# Schaltplan_Test_2.net
KiCad netlist of a schematic drawn in EAGLE
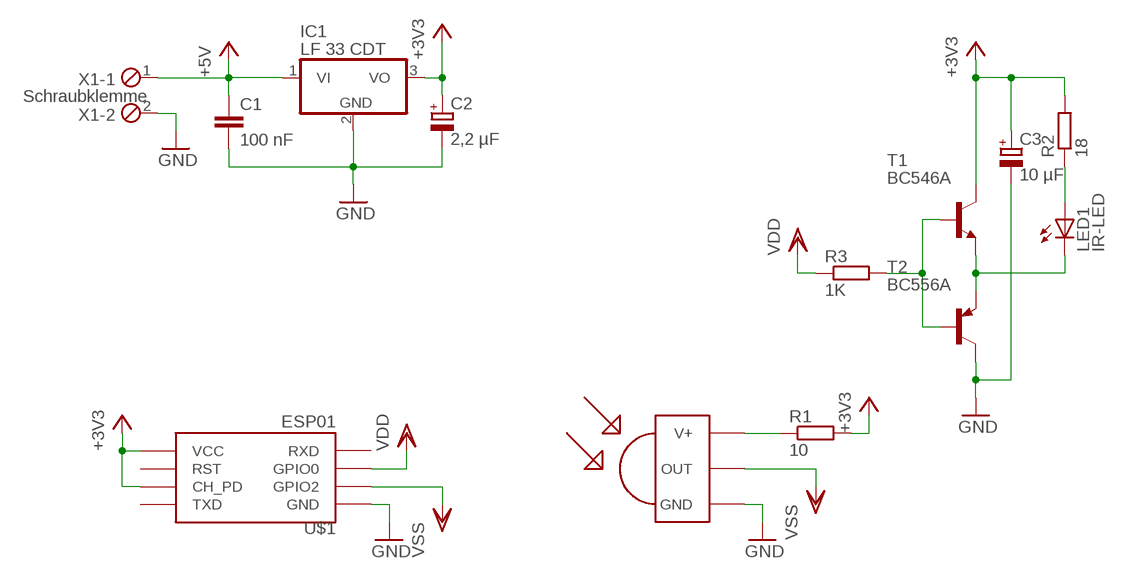
[diagram p0: schematic, sheet 1]

(export (version "E")
  (design (tool "Eeschema 10.0.6"))
  (components
    (comp (ref "C1")
      (value "100 nF")
      (footprint "eagle-import:C025-024X044")
      (libsource (lib "eagle-import") (part "C-EU025-024X044"))
    )
    (comp (ref "C2")
      (value "2,2 µF")
      (footprint "eagle-import:E2,5-5")
      (libsource (lib "eagle-import") (part "CPOL-EUE2.5-5"))
    )
    (comp (ref "C3")
      (value "10 µF")
      (footprint "eagle-import:E2,5-5")
      (libsource (lib "eagle-import") (part "CPOL-EUE2.5-5"))
    )
    (comp (ref "IC1")
      (value "LF 33 CDT")
      (footprint "eagle-import:TO220V")
      (libsource (lib "eagle-import") (part "MC78MT05AB"))
    )
    (comp (ref "IR-TRANSMITTER")
      (value "TSOP1833")
      (footprint "eagle-import:TSOP18XX")
      (libsource (lib "eagle-import") (part "TSOP1833"))
    )
    (comp (ref "LED1")
      (value "IR-LED")
      (footprint "eagle-import:LED5MM")
      (libsource (lib "eagle-import") (part "LED5MM"))
    )
    (comp (ref "R1")
      (value "10")
      (footprint "eagle-import:0204_7")
      (libsource (lib "eagle-import") (part "R-EU_0204/7"))
    )
    (comp (ref "R2")
      (value "18")
      (footprint "eagle-import:0204_5")
      (libsource (lib "eagle-import") (part "R-EU_0204/5"))
    )
    (comp (ref "R3")
      (value "1K")
      (footprint "eagle-import:0204_5")
      (libsource (lib "eagle-import") (part "R-EU_0204/5"))
    )
    (comp (ref "T1")
      (value "BC546A")
      (footprint "eagle-import:TO92-EBC")
      (libsource (lib "eagle-import") (part "BC546A"))
    )
    (comp (ref "T2")
      (value "BC556A")
      (footprint "eagle-import:TO92-EBC")
      (libsource (lib "eagle-import") (part "BC556A"))
    )
    (comp (ref "U$1")
      (value "ESP01")
      (footprint "eagle-import:ESP01")
      (libsource (lib "eagle-import") (part "ESP01"))
    )
    (comp (ref "X1")
      (value "Schraubklemme")
      (footprint "eagle-import:2POL254")
      (libsource (lib "eagle-import") (part "MPT2"))
    )
  )
  (nets
    (net (code "1") (name "+3V3") (class "Default")
      (node (ref "C2") (pin "+") (pinfunction "+_+") (pintype "passive"))
      (node (ref "C3") (pin "+") (pinfunction "+_+") (pintype "passive"))
      (node (ref "IC1") (pin "3") (pinfunction "VO_3") (pintype "passive"))
      (node (ref "R1") (pin "2") (pinfunction "2_2") (pintype "passive"))
      (node (ref "R2") (pin "2") (pinfunction "2_2") (pintype "passive"))
      (node (ref "T1") (pin "C") (pinfunction "C_C") (pintype "passive"))
      (node (ref "U$1") (pin "CH_PD") (pinfunction "CH_PD_CH_PD") (pintype "bidirectional"))
      (node (ref "U$1") (pin "VCC") (pinfunction "VCC_VCC") (pintype "bidirectional"))
    )
    (net (code "2") (name "+5V") (class "Default")
      (node (ref "C1") (pin "1") (pinfunction "1_1") (pintype "passive"))
      (node (ref "IC1") (pin "1") (pinfunction "VI_1") (pintype "input"))
      (node (ref "X1") (pin "1") (pinfunction "1_1") (pintype "passive"))
    )
    (net (code "3") (name "GND") (class "Default")
      (node (ref "C1") (pin "2") (pinfunction "2_2") (pintype "passive"))
      (node (ref "C2") (pin "-") (pinfunction "-_-") (pintype "passive"))
      (node (ref "C3") (pin "-") (pinfunction "-_-") (pintype "passive"))
      (node (ref "IC1") (pin "2") (pinfunction "GND_2") (pintype "passive"))
      (node (ref "IR-TRANSMITTER") (pin "GND") (pinfunction "GND_GND") (pintype "bidirectional"))
      (node (ref "T2") (pin "C") (pinfunction "C_C") (pintype "passive"))
      (node (ref "U$1") (pin "GND") (pinfunction "GND_GND") (pintype "bidirectional"))
      (node (ref "X1") (pin "2") (pinfunction "1_2") (pintype "passive"))
    )
    (net (code "4") (name "Net-(IR-TRANSMITTER-V+)") (class "Default")
      (node (ref "IR-TRANSMITTER") (pin "VCC") (pinfunction "V+_VCC") (pintype "bidirectional"))
      (node (ref "R1") (pin "1") (pinfunction "1_1") (pintype "passive"))
    )
    (net (code "5") (name "Net-(LED1-C)") (class "Default")
      (node (ref "LED1") (pin "K") (pinfunction "C_K") (pintype "passive"))
      (node (ref "T1") (pin "E") (pinfunction "E_E") (pintype "passive"))
      (node (ref "T2") (pin "E") (pinfunction "E_E") (pintype "passive"))
    )
    (net (code "6") (name "Net-(LED1-PadA)") (class "Default")
      (node (ref "LED1") (pin "A") (pinfunction "A_A") (pintype "passive"))
      (node (ref "R2") (pin "1") (pinfunction "1_1") (pintype "passive"))
    )
    (net (code "7") (name "Net-(R3-Pad2)") (class "Default")
      (node (ref "R3") (pin "2") (pinfunction "2_2") (pintype "passive"))
      (node (ref "T1") (pin "B") (pinfunction "B_B") (pintype "passive"))
      (node (ref "T2") (pin "B") (pinfunction "B_B") (pintype "passive"))
    )
    (net (code "8") (name "VDD") (class "Default")
      (node (ref "R3") (pin "1") (pinfunction "1_1") (pintype "passive"))
      (node (ref "U$1") (pin "GPIO0") (pinfunction "GPIO0_GPIO0") (pintype "bidirectional"))
    )
    (net (code "9") (name "VSS") (class "Default")
      (node (ref "IR-TRANSMITTER") (pin "OUT") (pinfunction "OUT_OUT") (pintype "bidirectional"))
      (node (ref "U$1") (pin "GPIO2") (pinfunction "GPIO2_GPIO2") (pintype "bidirectional"))
    )
    (net (code "10") (name "unconnected-(U$1-PadRST)") (class "Default")
      (node (ref "U$1") (pin "RST") (pinfunction "RST_RST") (pintype "bidirectional"))
    )
    (net (code "11") (name "unconnected-(U$1-RXD-PadRX)") (class "Default")
      (node (ref "U$1") (pin "RX") (pinfunction "RXD_RX") (pintype "bidirectional"))
    )
    (net (code "12") (name "unconnected-(U$1-TXD-PadTX)") (class "Default")
      (node (ref "U$1") (pin "TX") (pinfunction "TXD_TX") (pintype "bidirectional"))
    )
  )
)
